# BSK2.net
KiCad netlist of a schematic drawn in EAGLE
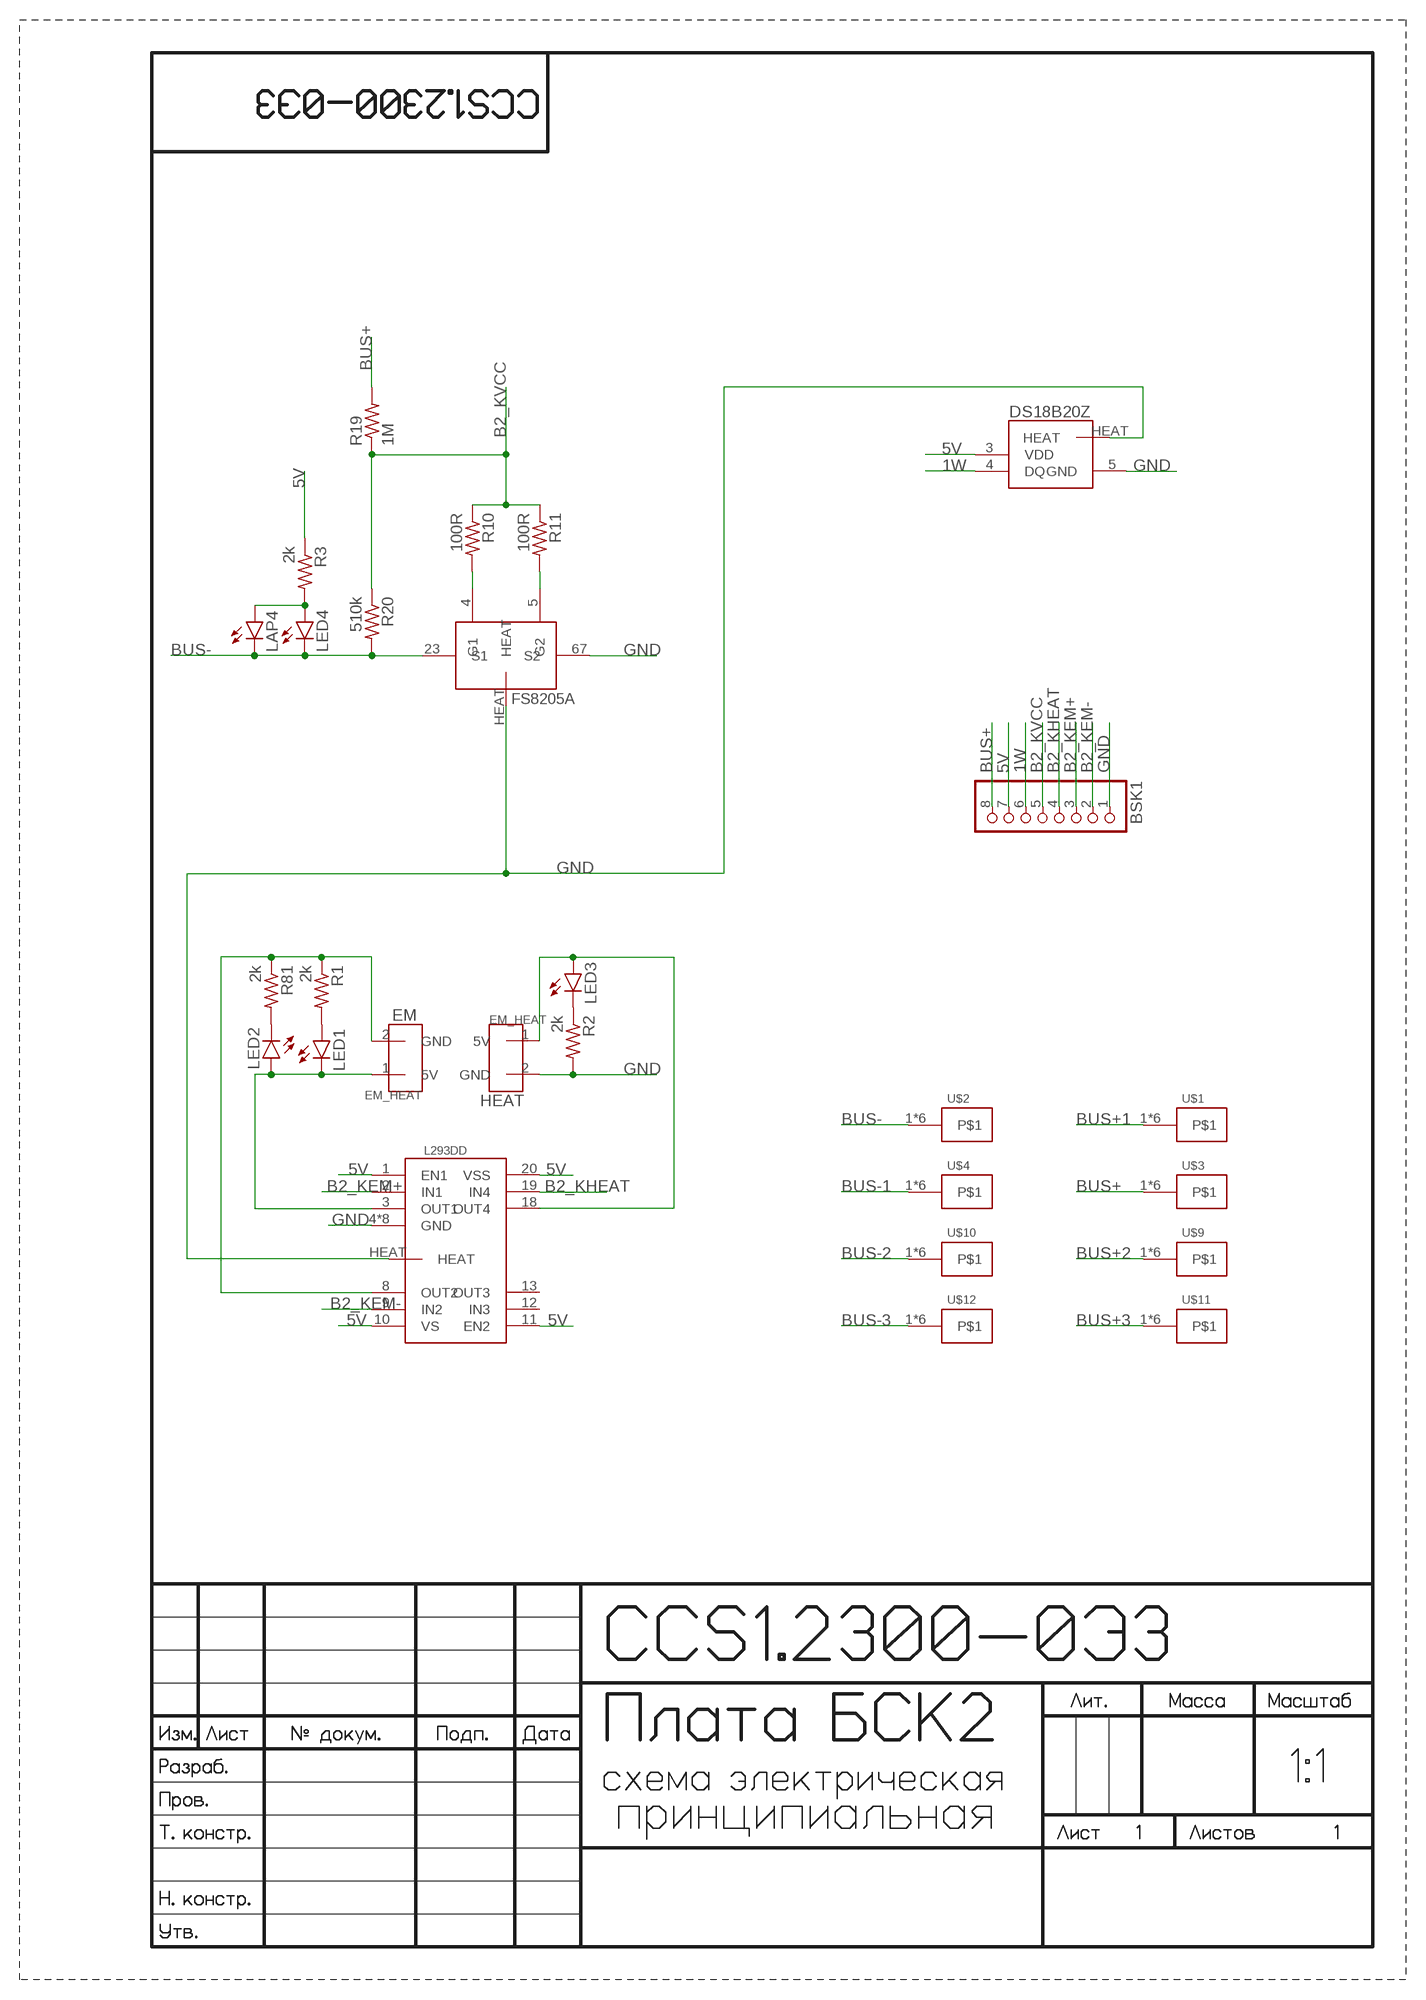
[diagram p0: schematic, sheet 1]

(export (version "E")
  (design (tool "Eeschema 10.0.6"))
  (components
    (comp (ref "BSK1")
      (value "PINHD-1X8")
      (footprint "eagle-import:1X08")
      (libsource (lib "eagle-import") (part "PINHD-1X8"))
    )
    (comp (ref "DS18B20Z")
      (value "DS18B20Z")
      (footprint "eagle-import:DS18B20Z")
      (libsource (lib "eagle-import") (part "DS18B20Z"))
    )
    (comp (ref "FS8205A")
      (value "FS8205A+")
      (footprint "eagle-import:FS8205A+")
      (libsource (lib "eagle-import") (part "FS8205A+"))
    )
    (comp (ref "L293DD")
      (value "L293DD")
      (footprint "eagle-import:L293DD")
      (libsource (lib "eagle-import") (part "L293DD"))
    )
    (comp (ref "LAP4")
      (value "LAP4-BOTTOM")
      (footprint "eagle-import:P47F-BOTTOM")
      (libsource (lib "eagle-import") (part "P4-BOTTOMLA"))
    )
    (comp (ref "LED1")
      (value "LEDCHIPLED_0603")
      (footprint "eagle-import:CHIPLED_0603")
      (libsource (lib "eagle-import") (part "LEDCHIPLED_0603"))
    )
    (comp (ref "LED2")
      (value "LEDCHIPLED_0603")
      (footprint "eagle-import:CHIPLED_0603")
      (libsource (lib "eagle-import") (part "LEDCHIPLED_0603"))
    )
    (comp (ref "LED3")
      (value "LEDCHIPLED_0603")
      (footprint "eagle-import:CHIPLED_0603")
      (libsource (lib "eagle-import") (part "LEDCHIPLED_0603"))
    )
    (comp (ref "LED4")
      (value "LEDCHIPLED_0603")
      (footprint "eagle-import:CHIPLED_0603")
      (libsource (lib "eagle-import") (part "LEDCHIPLED_0603"))
    )
    (comp (ref "R1")
      (value "2k")
      (footprint "eagle-import:R0603")
      (libsource (lib "eagle-import") (part "R-US_R0603"))
    )
    (comp (ref "R2")
      (value "2k")
      (footprint "eagle-import:R0603")
      (libsource (lib "eagle-import") (part "R-US_R0603"))
    )
    (comp (ref "R3")
      (value "2k")
      (footprint "eagle-import:R0603")
      (libsource (lib "eagle-import") (part "R-US_R0603"))
    )
    (comp (ref "R10")
      (value "100R")
      (footprint "eagle-import:R0603")
      (libsource (lib "eagle-import") (part "R-US_R0603"))
    )
    (comp (ref "R11")
      (value "100R")
      (footprint "eagle-import:R0603")
      (libsource (lib "eagle-import") (part "R-US_R0603"))
    )
    (comp (ref "R19")
      (value "1M")
      (footprint "eagle-import:R0603")
      (libsource (lib "eagle-import") (part "R-US_R0603"))
    )
    (comp (ref "R20")
      (value "510k")
      (footprint "eagle-import:R0603")
      (libsource (lib "eagle-import") (part "R-US_R0603"))
    )
    (comp (ref "R81")
      (value "2k")
      (footprint "eagle-import:R0603")
      (libsource (lib "eagle-import") (part "R-US_R0603"))
    )
    (comp (ref "U$1")
      (value "KCONNECT")
      (footprint "eagle-import:KCONNECT")
      (libsource (lib "eagle-import") (part "KCONNECT"))
    )
    (comp (ref "U$2")
      (value "KCONNECT")
      (footprint "eagle-import:KCONNECT")
      (libsource (lib "eagle-import") (part "KCONNECT"))
    )
    (comp (ref "U$3")
      (value "KCONNECT")
      (footprint "eagle-import:KCONNECT")
      (libsource (lib "eagle-import") (part "KCONNECT"))
    )
    (comp (ref "U$4")
      (value "KCONNECT")
      (footprint "eagle-import:KCONNECT")
      (libsource (lib "eagle-import") (part "KCONNECT"))
    )
    (comp (ref "U$6")
      (value "EM_HEAT")
      (footprint "eagle-import:EM_HEAT")
      (libsource (lib "eagle-import") (part "EM_HEAT"))
    )
    (comp (ref "U$7")
      (value "EM_HEAT")
      (footprint "eagle-import:EM_HEAT")
      (libsource (lib "eagle-import") (part "EM_HEAT"))
    )
    (comp (ref "U$9")
      (value "KCONNECT")
      (footprint "eagle-import:KCONNECT")
      (libsource (lib "eagle-import") (part "KCONNECT"))
    )
    (comp (ref "U$10")
      (value "KCONNECT")
      (footprint "eagle-import:KCONNECT")
      (libsource (lib "eagle-import") (part "KCONNECT"))
    )
    (comp (ref "U$11")
      (value "KCONNECT")
      (footprint "eagle-import:KCONNECT")
      (libsource (lib "eagle-import") (part "KCONNECT"))
    )
    (comp (ref "U$12")
      (value "KCONNECT")
      (footprint "eagle-import:KCONNECT")
      (libsource (lib "eagle-import") (part "KCONNECT"))
    )
  )
  (nets
    (net (code "1") (name "/1W") (class "Default")
      (node (ref "BSK1") (pin "6") (pinfunction "6_6") (pintype "passive"))
      (node (ref "DS18B20Z") (pin "4") (pinfunction "DQ_4") (pintype "bidirectional"))
    )
    (net (code "2") (name "/5V") (class "Default")
      (node (ref "BSK1") (pin "7") (pinfunction "7_7") (pintype "passive"))
      (node (ref "DS18B20Z") (pin "3") (pinfunction "VDD_3") (pintype "bidirectional"))
      (node (ref "L293DD") (pin "1") (pinfunction "EN1_1") (pintype "bidirectional"))
      (node (ref "L293DD") (pin "10") (pinfunction "VS_10") (pintype "bidirectional"))
      (node (ref "L293DD") (pin "11") (pinfunction "EN2_11") (pintype "bidirectional"))
      (node (ref "L293DD") (pin "20") (pinfunction "VSS_20") (pintype "bidirectional"))
      (node (ref "R3") (pin "1") (pinfunction "1_1") (pintype "passive"))
    )
    (net (code "3") (name "/B2_KEM+") (class "Default")
      (node (ref "BSK1") (pin "3") (pinfunction "3_3") (pintype "passive"))
      (node (ref "L293DD") (pin "2") (pinfunction "IN1_2") (pintype "bidirectional"))
    )
    (net (code "4") (name "/B2_KEM-") (class "Default")
      (node (ref "BSK1") (pin "2") (pinfunction "2_2") (pintype "passive"))
      (node (ref "L293DD") (pin "9") (pinfunction "IN2_9") (pintype "bidirectional"))
    )
    (net (code "5") (name "/B2_KHEAT") (class "Default")
      (node (ref "BSK1") (pin "4") (pinfunction "4_4") (pintype "passive"))
      (node (ref "L293DD") (pin "19") (pinfunction "IN4_19") (pintype "bidirectional"))
    )
    (net (code "6") (name "/B2_KVCC") (class "Default")
      (node (ref "BSK1") (pin "5") (pinfunction "5_5") (pintype "passive"))
      (node (ref "R10") (pin "1") (pinfunction "1_1") (pintype "passive"))
      (node (ref "R11") (pin "1") (pinfunction "1_1") (pintype "passive"))
      (node (ref "R19") (pin "1") (pinfunction "1_1") (pintype "passive"))
      (node (ref "R20") (pin "1") (pinfunction "1_1") (pintype "passive"))
    )
    (net (code "7") (name "/BUS+") (class "Default")
      (node (ref "BSK1") (pin "8") (pinfunction "8_8") (pintype "passive"))
      (node (ref "R19") (pin "2") (pinfunction "2_2") (pintype "passive"))
      (node (ref "U$3") (pin "1") (pinfunction "P$1_1") (pintype "bidirectional"))
      (node (ref "U$3") (pin "2") (pinfunction "P$1_2") (pintype "bidirectional"))
      (node (ref "U$3") (pin "3") (pinfunction "P$1_3") (pintype "bidirectional"))
      (node (ref "U$3") (pin "4") (pinfunction "P$1_4") (pintype "bidirectional"))
      (node (ref "U$3") (pin "P$1") (pinfunction "P$1_P$1") (pintype "bidirectional"))
      (node (ref "U$3") (pin "P$2") (pinfunction "P$1_P$2") (pintype "bidirectional"))
    )
    (net (code "8") (name "/BUS+1") (class "Default")
      (node (ref "U$1") (pin "1") (pinfunction "P$1_1") (pintype "bidirectional"))
      (node (ref "U$1") (pin "2") (pinfunction "P$1_2") (pintype "bidirectional"))
      (node (ref "U$1") (pin "3") (pinfunction "P$1_3") (pintype "bidirectional"))
      (node (ref "U$1") (pin "4") (pinfunction "P$1_4") (pintype "bidirectional"))
      (node (ref "U$1") (pin "P$1") (pinfunction "P$1_P$1") (pintype "bidirectional"))
      (node (ref "U$1") (pin "P$2") (pinfunction "P$1_P$2") (pintype "bidirectional"))
    )
    (net (code "9") (name "/BUS+2") (class "Default")
      (node (ref "U$9") (pin "1") (pinfunction "P$1_1") (pintype "bidirectional"))
      (node (ref "U$9") (pin "2") (pinfunction "P$1_2") (pintype "bidirectional"))
      (node (ref "U$9") (pin "3") (pinfunction "P$1_3") (pintype "bidirectional"))
      (node (ref "U$9") (pin "4") (pinfunction "P$1_4") (pintype "bidirectional"))
      (node (ref "U$9") (pin "P$1") (pinfunction "P$1_P$1") (pintype "bidirectional"))
      (node (ref "U$9") (pin "P$2") (pinfunction "P$1_P$2") (pintype "bidirectional"))
    )
    (net (code "10") (name "/BUS+3") (class "Default")
      (node (ref "U$11") (pin "1") (pinfunction "P$1_1") (pintype "bidirectional"))
      (node (ref "U$11") (pin "2") (pinfunction "P$1_2") (pintype "bidirectional"))
      (node (ref "U$11") (pin "3") (pinfunction "P$1_3") (pintype "bidirectional"))
      (node (ref "U$11") (pin "4") (pinfunction "P$1_4") (pintype "bidirectional"))
      (node (ref "U$11") (pin "P$1") (pinfunction "P$1_P$1") (pintype "bidirectional"))
      (node (ref "U$11") (pin "P$2") (pinfunction "P$1_P$2") (pintype "bidirectional"))
    )
    (net (code "11") (name "/BUS-") (class "Default")
      (node (ref "FS8205A") (pin "23") (pinfunction "S1_23") (pintype "bidirectional"))
      (node (ref "LAP4") (pin "C") (pinfunction "C_C") (pintype "passive"))
      (node (ref "LED4") (pin "C") (pinfunction "C_C") (pintype "passive"))
      (node (ref "R20") (pin "2") (pinfunction "2_2") (pintype "passive"))
      (node (ref "U$2") (pin "1") (pinfunction "P$1_1") (pintype "bidirectional"))
      (node (ref "U$2") (pin "2") (pinfunction "P$1_2") (pintype "bidirectional"))
      (node (ref "U$2") (pin "3") (pinfunction "P$1_3") (pintype "bidirectional"))
      (node (ref "U$2") (pin "4") (pinfunction "P$1_4") (pintype "bidirectional"))
      (node (ref "U$2") (pin "P$1") (pinfunction "P$1_P$1") (pintype "bidirectional"))
      (node (ref "U$2") (pin "P$2") (pinfunction "P$1_P$2") (pintype "bidirectional"))
    )
    (net (code "12") (name "/BUS-1") (class "Default")
      (node (ref "U$4") (pin "1") (pinfunction "P$1_1") (pintype "bidirectional"))
      (node (ref "U$4") (pin "2") (pinfunction "P$1_2") (pintype "bidirectional"))
      (node (ref "U$4") (pin "3") (pinfunction "P$1_3") (pintype "bidirectional"))
      (node (ref "U$4") (pin "4") (pinfunction "P$1_4") (pintype "bidirectional"))
      (node (ref "U$4") (pin "P$1") (pinfunction "P$1_P$1") (pintype "bidirectional"))
      (node (ref "U$4") (pin "P$2") (pinfunction "P$1_P$2") (pintype "bidirectional"))
    )
    (net (code "13") (name "/BUS-2") (class "Default")
      (node (ref "U$10") (pin "1") (pinfunction "P$1_1") (pintype "bidirectional"))
      (node (ref "U$10") (pin "2") (pinfunction "P$1_2") (pintype "bidirectional"))
      (node (ref "U$10") (pin "3") (pinfunction "P$1_3") (pintype "bidirectional"))
      (node (ref "U$10") (pin "4") (pinfunction "P$1_4") (pintype "bidirectional"))
      (node (ref "U$10") (pin "P$1") (pinfunction "P$1_P$1") (pintype "bidirectional"))
      (node (ref "U$10") (pin "P$2") (pinfunction "P$1_P$2") (pintype "bidirectional"))
    )
    (net (code "14") (name "/BUS-3") (class "Default")
      (node (ref "U$12") (pin "1") (pinfunction "P$1_1") (pintype "bidirectional"))
      (node (ref "U$12") (pin "2") (pinfunction "P$1_2") (pintype "bidirectional"))
      (node (ref "U$12") (pin "3") (pinfunction "P$1_3") (pintype "bidirectional"))
      (node (ref "U$12") (pin "4") (pinfunction "P$1_4") (pintype "bidirectional"))
      (node (ref "U$12") (pin "P$1") (pinfunction "P$1_P$1") (pintype "bidirectional"))
      (node (ref "U$12") (pin "P$2") (pinfunction "P$1_P$2") (pintype "bidirectional"))
    )
    (net (code "15") (name "/GND") (class "Default")
      (node (ref "BSK1") (pin "1") (pinfunction "1_1") (pintype "passive"))
      (node (ref "DS18B20Z") (pin "5") (pinfunction "GND_5") (pintype "bidirectional"))
      (node (ref "DS18B20Z") (pin "HEAT") (pinfunction "HEAT_HEAT") (pintype "bidirectional"))
      (node (ref "FS8205A") (pin "67") (pinfunction "S2_67") (pintype "bidirectional"))
      (node (ref "FS8205A") (pin "HEAT") (pinfunction "HEAT_HEAT") (pintype "bidirectional"))
      (node (ref "L293DD") (pin "14") (pinfunction "GND_14") (pintype "bidirectional"))
      (node (ref "L293DD") (pin "15") (pinfunction "GND_15") (pintype "bidirectional"))
      (node (ref "L293DD") (pin "16") (pinfunction "GND_16") (pintype "bidirectional"))
      (node (ref "L293DD") (pin "17") (pinfunction "GND_17") (pintype "bidirectional"))
      (node (ref "L293DD") (pin "4") (pinfunction "GND_4") (pintype "bidirectional"))
      (node (ref "L293DD") (pin "5") (pinfunction "GND_5") (pintype "bidirectional"))
      (node (ref "L293DD") (pin "6") (pinfunction "GND_6") (pintype "bidirectional"))
      (node (ref "L293DD") (pin "7") (pinfunction "GND_7") (pintype "bidirectional"))
      (node (ref "L293DD") (pin "HEAT") (pinfunction "HEAT_HEAT") (pintype "bidirectional"))
      (node (ref "R2") (pin "2") (pinfunction "2_2") (pintype "passive"))
      (node (ref "U$7") (pin "2") (pinfunction "GND_2") (pintype "bidirectional"))
    )
    (net (code "16") (name "Net-(FS8205A-G1)") (class "Default")
      (node (ref "FS8205A") (pin "4") (pinfunction "G1_4") (pintype "bidirectional"))
      (node (ref "R10") (pin "2") (pinfunction "2_2") (pintype "passive"))
    )
    (net (code "17") (name "Net-(FS8205A-G2)") (class "Default")
      (node (ref "FS8205A") (pin "5") (pinfunction "G2_5") (pintype "bidirectional"))
      (node (ref "R11") (pin "2") (pinfunction "2_2") (pintype "passive"))
    )
    (net (code "18") (name "Net-(L293DD-OUT1)") (class "Default")
      (node (ref "L293DD") (pin "3") (pinfunction "OUT1_3") (pintype "bidirectional"))
      (node (ref "LED1") (pin "C") (pinfunction "C_C") (pintype "passive"))
      (node (ref "LED2") (pin "A") (pinfunction "A_A") (pintype "passive"))
      (node (ref "U$6") (pin "1") (pinfunction "5V_1") (pintype "bidirectional"))
    )
    (net (code "19") (name "Net-(L293DD-OUT2)") (class "Default")
      (node (ref "L293DD") (pin "8") (pinfunction "OUT2_8") (pintype "bidirectional"))
      (node (ref "R1") (pin "1") (pinfunction "1_1") (pintype "passive"))
      (node (ref "R81") (pin "1") (pinfunction "1_1") (pintype "passive"))
      (node (ref "U$6") (pin "2") (pinfunction "GND_2") (pintype "bidirectional"))
    )
    (net (code "20") (name "Net-(L293DD-OUT4)") (class "Default")
      (node (ref "L293DD") (pin "18") (pinfunction "OUT4_18") (pintype "bidirectional"))
      (node (ref "LED3") (pin "A") (pinfunction "A_A") (pintype "passive"))
      (node (ref "U$7") (pin "1") (pinfunction "5V_1") (pintype "bidirectional"))
    )
    (net (code "21") (name "Net-(LAP4-PadA)") (class "Default")
      (node (ref "LAP4") (pin "A") (pinfunction "A_A") (pintype "passive"))
      (node (ref "LED4") (pin "A") (pinfunction "A_A") (pintype "passive"))
      (node (ref "R3") (pin "2") (pinfunction "2_2") (pintype "passive"))
    )
    (net (code "22") (name "Net-(LED1-PadA)") (class "Default")
      (node (ref "LED1") (pin "A") (pinfunction "A_A") (pintype "passive"))
      (node (ref "R1") (pin "2") (pinfunction "2_2") (pintype "passive"))
    )
    (net (code "23") (name "Net-(LED2-PadC)") (class "Default")
      (node (ref "LED2") (pin "C") (pinfunction "C_C") (pintype "passive"))
      (node (ref "R81") (pin "2") (pinfunction "2_2") (pintype "passive"))
    )
    (net (code "24") (name "Net-(LED3-PadC)") (class "Default")
      (node (ref "LED3") (pin "C") (pinfunction "C_C") (pintype "passive"))
      (node (ref "R2") (pin "1") (pinfunction "1_1") (pintype "passive"))
    )
    (net (code "25") (name "unconnected-(L293DD-IN3-Pad12)") (class "Default")
      (node (ref "L293DD") (pin "12") (pinfunction "IN3_12") (pintype "bidirectional"))
    )
    (net (code "26") (name "unconnected-(L293DD-OUT3-Pad13)") (class "Default")
      (node (ref "L293DD") (pin "13") (pinfunction "OUT3_13") (pintype "bidirectional"))
    )
  )
)
